# Auxiliary.net
KiCad netlist of a schematic drawn in Altium Designer
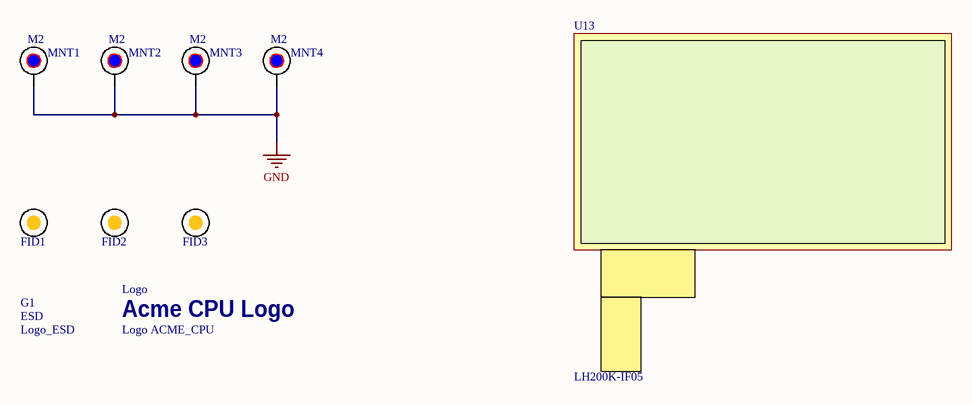
[diagram p0: Auxiliary.SchDoc]

(export (version "E")
  (design (tool "Eeschema 10.0.6"))
  (components
    (comp (ref "FID1")
      (value "N/A")
      (footprint "Fiducial")
      (description "Fiducial mark.  There is nothing to buy or mount.")
      (libsource (lib "altium-import") (part "root_0_Fiducial_"))
    )
    (comp (ref "FID2")
      (value "N/A")
      (footprint "Fiducial")
      (description "Fiducial mark.  There is nothing to buy or mount.")
      (libsource (lib "altium-import") (part "root_0_Fiducial_"))
    )
    (comp (ref "FID3")
      (value "N/A")
      (footprint "Fiducial")
      (description "Fiducial mark.  There is nothing to buy or mount.")
      (libsource (lib "altium-import") (part "root_0_Fiducial_"))
    )
    (comp (ref "G1")
      (value "Logo_ESD")
      (footprint "Logo_ESD")
      (libsource (lib "altium-import") (part "root_0_Logo_ESD_"))
    )
    (comp (ref "Logo")
      (value "Logo ACME_CPU")
      (footprint "LOGO_ACME_CPU")
      (libsource (lib "BLDC_Motor_Driver") (part "Logo ACME_CPU"))
    )
    (comp (ref "MNT1")
      (value "MountHole M2. Nothing to buy or mount")
      (footprint "MountHole_M2")
      (description "PCB Mount Hole. There is nothing to buy or mount.")
      (libsource (lib "BLDC_Motor_Driver") (part "MountHole_M2"))
    )
    (comp (ref "MNT2")
      (value "MountHole M2. Nothing to buy or mount")
      (footprint "MountHole_M2")
      (description "PCB Mount Hole. There is nothing to buy or mount.")
      (libsource (lib "BLDC_Motor_Driver") (part "MountHole_M2"))
    )
    (comp (ref "MNT3")
      (value "MountHole M2. Nothing to buy or mount")
      (footprint "MountHole_M2")
      (description "PCB Mount Hole. There is nothing to buy or mount.")
      (libsource (lib "BLDC_Motor_Driver") (part "MountHole_M2"))
    )
    (comp (ref "MNT4")
      (value "MountHole M2. Nothing to buy or mount")
      (footprint "MountHole_M2")
      (description "PCB Mount Hole. There is nothing to buy or mount.")
      (libsource (lib "BLDC_Motor_Driver") (part "MountHole_M2"))
    )
    (comp (ref "U13")
      (value "LH200K-IF05")
      (description "2” TFT LCD Display.")
      (fields (field (name "MANUFACTURER") "Shenzhen Limito Technology Inc."))
      (libsource (lib "BLDC_Motor_Driver") (part "MOD LH200K-IF05 240x320 2-inch TFT LCD Display"))
    )
  )
  (nets
    (net (code "1") (name "GND") (class "Default")
      (node (ref "MNT1") (pin "1") (pintype "passive"))
      (node (ref "MNT2") (pin "1") (pintype "passive"))
      (node (ref "MNT3") (pin "1") (pintype "passive"))
      (node (ref "MNT4") (pin "1") (pintype "passive"))
    )
  )
)
